# 1-Regulator.net
KiCad netlist of a schematic drawn in Altium Designer
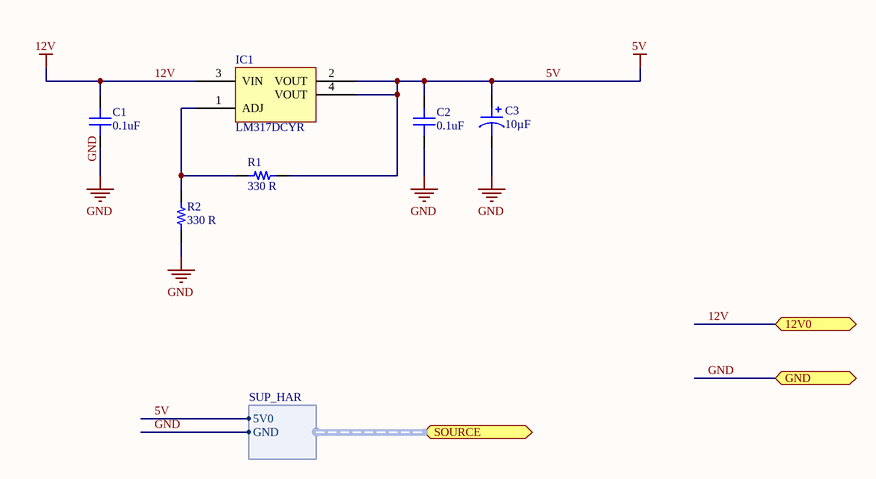
[diagram p0: 1-Regulator.SchDoc]

(export (version "E")
  (design (tool "Eeschema 10.0.6"))
  (components
    (comp (ref "C1")
      (value "0.1uF")
      (footprint "CAP 0805_2012")
      (description "CAP CER 5.6PF 500V C0G/NP0 0805")
      (fields (field (name "PART NUMBER") "CBR08C569BCGAC") (field (name "MANUFACTURER") "KEMET"))
      (libsource (lib "Celestial Altium Library - altium_library") (part "Capacitor"))
    )
    (comp (ref "C2")
      (value "0.1uF")
      (footprint "CAP 0805_2012")
      (description "CAP CER 5.6PF 500V C0G/NP0 0805")
      (fields (field (name "PART NUMBER") "CBR08C569BCGAC") (field (name "MANUFACTURER") "KEMET"))
      (libsource (lib "Celestial Altium Library - altium_library") (part "Capacitor"))
    )
    (comp (ref "C3")
      (value "10µF")
      (footprint "CAP POL 1206_3216")
      (description "CAP TANT 33UF 10% 6.3V 1206")
      (fields (field (name "PART NUMBER") "TR3A336K6R3C0600") (field (name "MANUFACTURER") "Vishay Sprague"))
      (libsource (lib "Celestial Altium Library - altium_library") (part "Polarised Capacitor"))
    )
    (comp (ref "IC1")
      (value "LM317DCYR")
      (footprint "TI SOT-223 DCY")
      (description "IC REG LIN POS ADJ 1.5A SOT223-4")
      (fields (field (name "MANUFACTURER") "Texas Instruments"))
      (libsource (lib "Celestial Altium Library - altium_library") (part "TI LM317-N"))
    )
    (comp (ref "R1")
      (value "330 R")
      (footprint "RES 0805_2012")
      (description "RES 82K OHM 0.5% 1/8W 0805")
      (fields
        (field (name "PART NUMBER") "RNCF0805DTE82K0")
        (field (name "MANUFACTURER") "Stackpole Electronics Inc")
      )
      (libsource (lib "Celestial Altium Library - altium_library") (part "Resistor"))
    )
    (comp (ref "R2")
      (value "330 R")
      (footprint "RES 0805_2012")
      (description "RES 82K OHM 0.5% 1/8W 0805")
      (fields
        (field (name "PART NUMBER") "RNCF0805DTE82K0")
        (field (name "MANUFACTURER") "Stackpole Electronics Inc")
      )
      (libsource (lib "Celestial Altium Library - altium_library") (part "Resistor"))
    )
  )
  (nets
    (net (code "3") (name "5V") (class "Default")
      (node (ref "C2") (pin "2") (pinfunction "2_2") (pintype "passive"))
      (node (ref "C3") (pin "1") (pinfunction "1_1") (pintype "passive"))
      (node (ref "IC1") (pin "2") (pinfunction "VOUT_2") (pintype "passive"))
      (node (ref "IC1") (pin "4") (pinfunction "VOUT_4") (pintype "passive"))
      (node (ref "R1") (pin "2") (pinfunction "2_2") (pintype "passive"))
    )
    (net (code "4") (name "12V") (class "Default")
      (node (ref "C1") (pin "2") (pinfunction "2_2") (pintype "passive"))
      (node (ref "IC1") (pin "3") (pinfunction "VIN_3") (pintype "passive"))
    )
    (net (code "5") (name "GND") (class "Default")
      (node (ref "C1") (pin "1") (pinfunction "1_1") (pintype "passive"))
      (node (ref "C2") (pin "1") (pinfunction "1_1") (pintype "passive"))
      (node (ref "C3") (pin "2") (pinfunction "2_2") (pintype "passive"))
      (node (ref "R2") (pin "1") (pinfunction "1_1") (pintype "passive"))
    )
    (net (code "6") (name "Net-(IC1-ADJ)") (class "Default")
      (node (ref "IC1") (pin "1") (pinfunction "ADJ_1") (pintype "passive"))
      (node (ref "R1") (pin "1") (pinfunction "1_1") (pintype "passive"))
      (node (ref "R2") (pin "2") (pinfunction "2_2") (pintype "passive"))
    )
  )
)
